# thermostat-v1.net
KiCad netlist of a schematic drawn in EAGLE
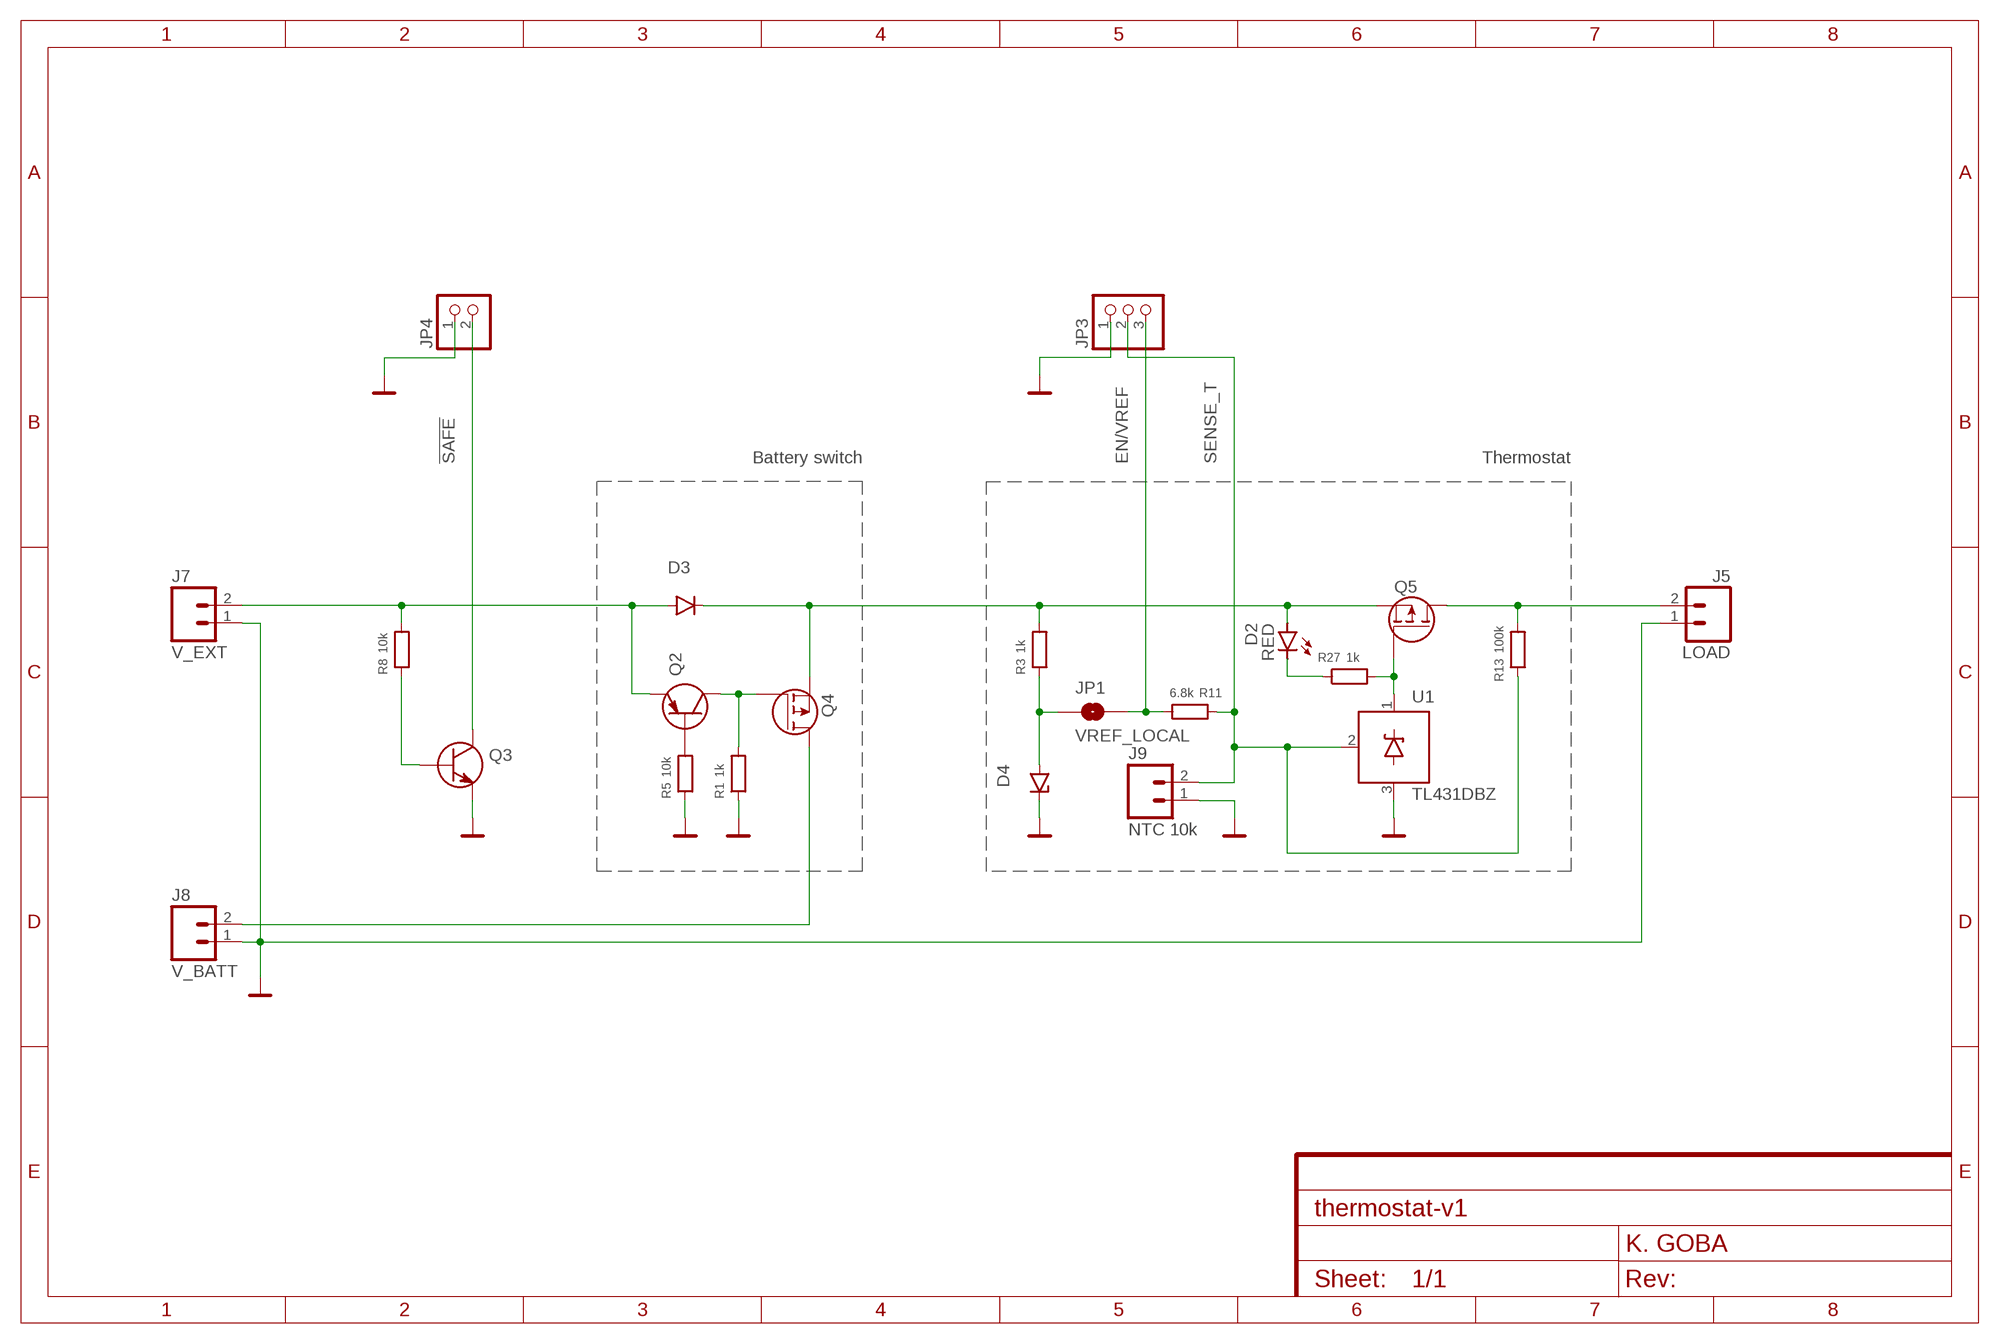
[diagram p0: schematic, sheet 1]

(export (version "E")
  (design (tool "Eeschema 10.0.6"))
  (components
    (comp (ref "D2")
      (value "RED")
      (footprint "eagle-import:R0805")
      (libsource (lib "eagle-import") (part "LED0805"))
    )
    (comp (ref "D3")
      (value "DIODE-SMA-ALT")
      (footprint "eagle-import:D-SMA-ALT")
      (libsource (lib "eagle-import") (part "DIODE-SMA-ALT"))
    )
    (comp (ref "D4")
      (value "DIODE-ZENER-SOD80")
      (footprint "eagle-import:SOD80")
      (libsource (lib "eagle-import") (part "DIODE-ZENER-SOD80"))
    )
    (comp (ref "J5")
      (value "LOAD")
      (footprint "eagle-import:SCREWTERMINAL-3.5MM-2")
      (libsource (lib "eagle-import") (part "M2-3.50MM"))
    )
    (comp (ref "J7")
      (value "V_EXT")
      (footprint "eagle-import:SCREWTERMINAL-3.5MM-2")
      (libsource (lib "eagle-import") (part "M2-3.50MM"))
    )
    (comp (ref "J8")
      (value "V_BATT")
      (footprint "eagle-import:JST-2-PTH")
      (libsource (lib "eagle-import") (part "M2-2MM-JST-H"))
    )
    (comp (ref "J9")
      (value "NTC 10k")
      (footprint "eagle-import:1X02")
      (libsource (lib "eagle-import") (part "M2-2.54MM"))
    )
    (comp (ref "JP1")
      (value "VREF_LOCAL")
      (footprint "eagle-import:SMT-JUMPER_2_NO_NO-SILK")
      (libsource (lib "eagle-import") (part "JUMPER-SMT_2_NO_NO-SILK"))
    )
    (comp (ref "JP3")
      (value "PINHD-1X3")
      (footprint "eagle-import:1X03")
      (libsource (lib "eagle-import") (part "PINHD-1X3"))
    )
    (comp (ref "JP4")
      (value "PINHD-1X2")
      (footprint "eagle-import:1X02")
      (libsource (lib "eagle-import") (part "PINHD-1X2"))
    )
    (comp (ref "Q2")
      (value "BJT-PNPSMD")
      (footprint "eagle-import:SOT23-3")
      (libsource (lib "eagle-import") (part "BJT-PNPSMD"))
    )
    (comp (ref "Q3")
      (value "BJT-NPN-SOT23-3")
      (footprint "eagle-import:SOT23-3")
      (libsource (lib "eagle-import") (part "BJT-NPN-SOT23-3"))
    )
    (comp (ref "Q4")
      (value "MOSFET-P-SOT23-3")
      (footprint "eagle-import:SOT23-3")
      (libsource (lib "eagle-import") (part "MOSFET-P-SOT23-3"))
    )
    (comp (ref "Q5")
      (value "MOSFET-P-SOT23-3")
      (footprint "eagle-import:SOT23-3")
      (libsource (lib "eagle-import") (part "MOSFET-P-SOT23-3"))
    )
    (comp (ref "R1")
      (value "1k")
      (footprint "eagle-import:R0603")
      (libsource (lib "eagle-import") (part "RESISTOR-0603"))
    )
    (comp (ref "R3")
      (value "1k")
      (footprint "eagle-import:R0603")
      (libsource (lib "eagle-import") (part "RESISTOR-0603"))
    )
    (comp (ref "R5")
      (value "10k")
      (footprint "eagle-import:R0603")
      (libsource (lib "eagle-import") (part "RESISTOR-0603"))
    )
    (comp (ref "R8")
      (value "10k")
      (footprint "eagle-import:R0603")
      (libsource (lib "eagle-import") (part "RESISTOR-0603"))
    )
    (comp (ref "R11")
      (value "6.8k")
      (footprint "eagle-import:R0603")
      (libsource (lib "eagle-import") (part "RESISTOR-0603"))
    )
    (comp (ref "R13")
      (value "100k")
      (footprint "eagle-import:R0603")
      (libsource (lib "eagle-import") (part "RESISTOR-0603"))
    )
    (comp (ref "R27")
      (value "1k")
      (footprint "eagle-import:R0603")
      (libsource (lib "eagle-import") (part "RESISTOR-0603"))
    )
    (comp (ref "U1")
      (value "TL431DBZ")
      (footprint "eagle-import:SOT23-3")
      (libsource (lib "eagle-import") (part "TL431DBZ"))
    )
  )
  (nets
    (net (code "1") (name "/EN{slash}VREF") (class "Default")
      (node (ref "JP1") (pin "2") (pinfunction "2_2") (pintype "passive"))
      (node (ref "JP3") (pin "3") (pinfunction "3_3") (pintype "passive"))
      (node (ref "R11") (pin "2") (pinfunction "2_2") (pintype "passive"))
    )
    (net (code "2") (name "/SENSE_T") (class "Default")
      (node (ref "J9") (pin "2") (pinfunction "2_2") (pintype "passive"))
      (node (ref "JP3") (pin "2") (pinfunction "2_2") (pintype "passive"))
      (node (ref "R11") (pin "1") (pinfunction "1_1") (pintype "passive"))
      (node (ref "R13") (pin "1") (pinfunction "1_1") (pintype "passive"))
      (node (ref "U1") (pin "2") (pinfunction "R_2") (pintype "bidirectional"))
    )
    (net (code "3") (name "/~{SAFE}") (class "Default")
      (node (ref "JP4") (pin "2") (pinfunction "2_2") (pintype "passive"))
      (node (ref "Q3") (pin "3") (pinfunction "C_3") (pintype "passive"))
    )
    (net (code "4") (name "GND") (class "Default")
      (node (ref "D4") (pin "C") (pinfunction "C_C") (pintype "passive"))
      (node (ref "J5") (pin "1") (pinfunction "1_1") (pintype "passive"))
      (node (ref "J7") (pin "1") (pinfunction "1_1") (pintype "passive"))
      (node (ref "J8") (pin "1") (pinfunction "1_1") (pintype "passive"))
      (node (ref "J9") (pin "1") (pinfunction "1_1") (pintype "passive"))
      (node (ref "JP3") (pin "1") (pinfunction "1_1") (pintype "passive"))
      (node (ref "JP4") (pin "1") (pinfunction "1_1") (pintype "passive"))
      (node (ref "Q3") (pin "2") (pinfunction "E_2") (pintype "passive"))
      (node (ref "R1") (pin "1") (pinfunction "1_1") (pintype "passive"))
      (node (ref "R5") (pin "1") (pinfunction "1_1") (pintype "passive"))
      (node (ref "U1") (pin "3") (pinfunction "A_3") (pintype "bidirectional"))
    )
    (net (code "5") (name "Net-(D2-A)") (class "Default")
      (node (ref "D2") (pin "1") (pinfunction "A_1") (pintype "passive"))
      (node (ref "D3") (pin "C") (pinfunction "C_C") (pintype "passive"))
      (node (ref "Q4") (pin "2") (pinfunction "S_2") (pintype "passive"))
      (node (ref "Q5") (pin "2") (pinfunction "S_2") (pintype "passive"))
      (node (ref "R3") (pin "2") (pinfunction "2_2") (pintype "passive"))
    )
    (net (code "6") (name "Net-(D2-C)") (class "Default")
      (node (ref "D2") (pin "2") (pinfunction "C_2") (pintype "passive"))
      (node (ref "R27") (pin "1") (pinfunction "1_1") (pintype "passive"))
    )
    (net (code "7") (name "Net-(D4-PadA)") (class "Default")
      (node (ref "D4") (pin "A") (pinfunction "A_A") (pintype "passive"))
      (node (ref "JP1") (pin "1") (pinfunction "1_1") (pintype "passive"))
      (node (ref "R3") (pin "1") (pinfunction "1_1") (pintype "passive"))
    )
    (net (code "8") (name "Net-(Q2-B)") (class "Default")
      (node (ref "Q2") (pin "1") (pinfunction "B_1") (pintype "passive"))
      (node (ref "R5") (pin "2") (pinfunction "2_2") (pintype "passive"))
    )
    (net (code "9") (name "Net-(Q2-C)") (class "Default")
      (node (ref "Q2") (pin "3") (pinfunction "C_3") (pintype "passive"))
      (node (ref "Q4") (pin "1") (pinfunction "G_1") (pintype "passive"))
      (node (ref "R1") (pin "2") (pinfunction "2_2") (pintype "passive"))
    )
    (net (code "10") (name "Net-(Q2-E)") (class "Default")
      (node (ref "D3") (pin "A") (pinfunction "A_A") (pintype "passive"))
      (node (ref "J7") (pin "2") (pinfunction "2_2") (pintype "passive"))
      (node (ref "Q2") (pin "2") (pinfunction "E_2") (pintype "passive"))
      (node (ref "R8") (pin "2") (pinfunction "2_2") (pintype "passive"))
    )
    (net (code "11") (name "Net-(Q3-B)") (class "Default")
      (node (ref "Q3") (pin "1") (pinfunction "B_1") (pintype "passive"))
      (node (ref "R8") (pin "1") (pinfunction "1_1") (pintype "passive"))
    )
    (net (code "12") (name "Net-(Q4-D)") (class "Default")
      (node (ref "J8") (pin "2") (pinfunction "2_2") (pintype "passive"))
      (node (ref "Q4") (pin "3") (pinfunction "D_3") (pintype "passive"))
    )
    (net (code "13") (name "Net-(Q5-D)") (class "Default")
      (node (ref "J5") (pin "2") (pinfunction "2_2") (pintype "passive"))
      (node (ref "Q5") (pin "3") (pinfunction "D_3") (pintype "passive"))
      (node (ref "R13") (pin "2") (pinfunction "2_2") (pintype "passive"))
    )
    (net (code "14") (name "Net-(Q5-G)") (class "Default")
      (node (ref "Q5") (pin "1") (pinfunction "G_1") (pintype "passive"))
      (node (ref "R27") (pin "2") (pinfunction "2_2") (pintype "passive"))
      (node (ref "U1") (pin "1") (pinfunction "C_1") (pintype "bidirectional"))
    )
  )
)
